# RTC.net
KiCad netlist of a schematic drawn in Altium Designer
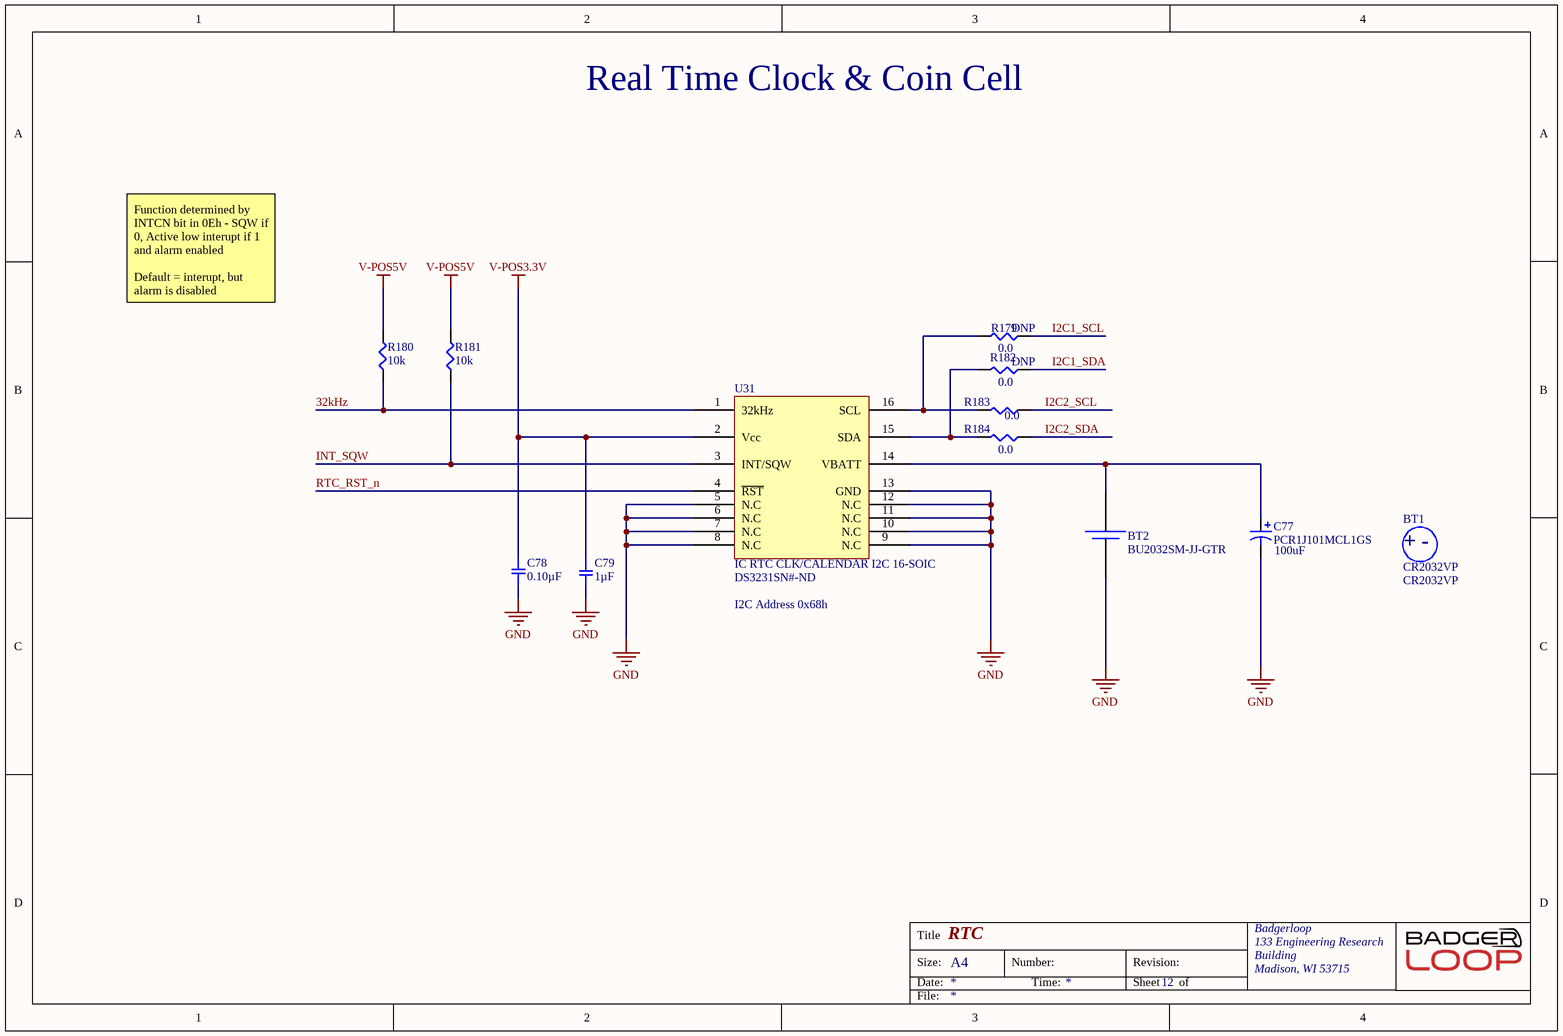
[diagram p0: RTC.SchDoc]

(export (version "E")
  (design (tool "Eeschema 10.0.6"))
  (components
    (comp (ref "BT1")
      (value "CR2032VP")
      (description "BATTERY LITHIUM 3V COIN 20MM")
      (fields (field (name "MANUFACTURER") "Energizer") (field (name "MANUFACTURER PART NUMBER") "CR2032VP"))
      (libsource (lib "misc") (part "CR2032VP"))
    )
    (comp (ref "BT2")
      (value "BU2032SM-JJ-GTR")
      (footprint "BATTERY HOLDER COIN 20MM")
      (description "HOLDER COIN CELL 2032 SMD")
      (fields (field (name "MANUFACTURER") "Memory Protection Devices"))
      (libsource (lib "misc") (part "BU2032SM-JJ-GTR"))
    )
    (comp (ref "C77")
      (value "PCR1J101MCL1GS")
      (footprint "CAPAE110103X126M")
      (description "CAP ALUM POLY 100UF 20% 63V SMD")
      (fields
        (field (name "MANUFACTURER") "Nichicon")
        (field (name "CAPACITANCE") "100uF")
        (field (name "TOLERANCE") "20%")
      )
      (libsource (lib "capacitors") (part "PCR1J101MCL1GS"))
    )
    (comp (ref "C78")
      (value "0.10µF")
      (footprint "SMD-0805C")
      (description "CAP CER 0.1UF 16V X7R 0805")
      (fields
        (field (name "DIGI-KEY PART NUMBER") "490-12557-1-ND")
        (field (name "PART NUMBER") "GRM219R71C104JA01D")
      )
      (libsource (lib "capacitors") (part "GRM219R71C104JA01D"))
    )
    (comp (ref "C79")
      (value "1µF")
      (footprint "SMD-0805C")
      (description "CAP CER 1UF 50V X7R 0805")
      (fields
        (field (name "DIGI-KEY PART NUMBER") "490-4736-1-ND")
        (field (name "PART NUMBER") "GRM21BR71H105KA12L")
      )
      (libsource (lib "capacitors") (part "GRM21BR71H105KA12L"))
    )
    (comp (ref "R179")
      (value "0.0")
      (footprint "SMD-0805-RES")
      (description "RES SMD 0.0 OHM JUMPER 1/8W 0805")
      (fields
        (field (name "PART NUMBER") "ERJ-6GEY0R00V")
        (field (name "DIGI-KEY PART NUMBER") "P0.0ACT-ND")
        (field (name "DNP") "DNP")
      )
      (libsource (lib "resistors") (part "ERJ-6GEY0R00V"))
    )
    (comp (ref "R180")
      (value "10k")
      (footprint "SMD-0805-RES")
      (description "RES SMD 10K OHM 5% 1/2W 0805")
      (fields (field (name "PART NUMBER") "ERJ-P06J103V") (field (name "DIGI-KEY PART NUMBER") "P10KADCT-ND"))
      (libsource (lib "resistors") (part "ERJ-P06J103V"))
    )
    (comp (ref "R181")
      (value "10k")
      (footprint "SMD-0805-RES")
      (description "RES SMD 10K OHM 5% 1/2W 0805")
      (fields (field (name "PART NUMBER") "ERJ-P06J103V") (field (name "DIGI-KEY PART NUMBER") "P10KADCT-ND"))
      (libsource (lib "resistors") (part "ERJ-P06J103V"))
    )
    (comp (ref "R182")
      (value "0.0")
      (footprint "SMD-0805-RES")
      (description "RES SMD 0.0 OHM JUMPER 1/8W 0805")
      (fields
        (field (name "PART NUMBER") "ERJ-6GEY0R00V")
        (field (name "DIGI-KEY PART NUMBER") "P0.0ACT-ND")
        (field (name "DNP") "DNP")
      )
      (libsource (lib "resistors") (part "ERJ-6GEY0R00V"))
    )
    (comp (ref "R183")
      (value "0.0")
      (footprint "SMD-0805-RES")
      (description "RES SMD 0.0 OHM JUMPER 1/8W 0805")
      (fields (field (name "PART NUMBER") "ERJ-6GEY0R00V") (field (name "DIGI-KEY PART NUMBER") "P0.0ACT-ND"))
      (libsource (lib "resistors") (part "ERJ-6GEY0R00V"))
    )
    (comp (ref "R184")
      (value "0.0")
      (footprint "SMD-0805-RES")
      (description "RES SMD 0.0 OHM JUMPER 1/8W 0805")
      (fields (field (name "PART NUMBER") "ERJ-6GEY0R00V") (field (name "DIGI-KEY PART NUMBER") "P0.0ACT-ND"))
      (libsource (lib "resistors") (part "ERJ-6GEY0R00V"))
    )
    (comp (ref "U31")
      (value "IC RTC CLK/CALENDAR I2C 16-SOIC")
      (footprint "SOP127P1030X265-16N")
      (fields
        (field (name "MANUFACTURER") "Maxim")
        (field (name "MANUFACTURER PART NUMBER") "DS3231SN#")
        (field (name "SUPPLIER PART NUMBER 1") "DS3231SN#-ND")
      )
      (libsource (lib "ic") (part "DS3231"))
    )
  )
  (nets
    (net (code "1") (name "/32kHz") (class "Default")
      (node (ref "R180") (pin "1") (pinfunction "1_1") (pintype "passive"))
      (node (ref "U31") (pin "1") (pinfunction "32kHz_1") (pintype "passive"))
    )
    (net (code "2") (name "/I2C1_SCL") (class "Default")
      (node (ref "R179") (pin "1") (pinfunction "1_1") (pintype "passive"))
    )
    (net (code "3") (name "/I2C1_SDA") (class "Default")
      (node (ref "R182") (pin "1") (pinfunction "1_1") (pintype "passive"))
    )
    (net (code "4") (name "/I2C2_SCL") (class "Default")
      (node (ref "R183") (pin "1") (pinfunction "1_1") (pintype "passive"))
    )
    (net (code "5") (name "/I2C2_SDA") (class "Default")
      (node (ref "R184") (pin "1") (pinfunction "1_1") (pintype "passive"))
    )
    (net (code "6") (name "/INT_SQW") (class "Default")
      (node (ref "R181") (pin "1") (pinfunction "1_1") (pintype "passive"))
      (node (ref "U31") (pin "3") (pinfunction "INT/SQW_3") (pintype "passive"))
    )
    (net (code "7") (name "/RTC_RST_n") (class "Default")
      (node (ref "U31") (pin "4") (pinfunction "RST_4") (pintype "passive"))
    )
    (net (code "8") (name "GND") (class "Default")
      (node (ref "BT2") (pin "1") (pinfunction "+_1") (pintype "passive"))
      (node (ref "C77") (pin "2") (pinfunction "2_2") (pintype "passive"))
      (node (ref "C78") (pin "1") (pinfunction "1_1") (pintype "passive"))
      (node (ref "C79") (pin "2") (pinfunction "2_2") (pintype "passive"))
      (node (ref "U31") (pin "10") (pinfunction "N.C_10") (pintype "passive"))
      (node (ref "U31") (pin "11") (pinfunction "N.C_11") (pintype "passive"))
      (node (ref "U31") (pin "12") (pinfunction "N.C_12") (pintype "passive"))
      (node (ref "U31") (pin "13") (pinfunction "GND_13") (pintype "passive"))
      (node (ref "U31") (pin "5") (pinfunction "N.C_5") (pintype "passive"))
      (node (ref "U31") (pin "6") (pinfunction "N.C_6") (pintype "passive"))
      (node (ref "U31") (pin "7") (pinfunction "N.C_7") (pintype "passive"))
      (node (ref "U31") (pin "8") (pinfunction "N.C_8") (pintype "passive"))
      (node (ref "U31") (pin "9") (pinfunction "N.C_9") (pintype "passive"))
    )
    (net (code "9") (name "Net-(BT2--)") (class "Default")
      (node (ref "BT2") (pin "2") (pinfunction "-_2") (pintype "passive"))
      (node (ref "C77") (pin "1") (pinfunction "1_1") (pintype "passive"))
      (node (ref "U31") (pin "14") (pinfunction "VBATT_14") (pintype "passive"))
    )
    (net (code "10") (name "Net-(U31-SCL)") (class "Default")
      (node (ref "R179") (pin "2") (pinfunction "2_2") (pintype "passive"))
      (node (ref "R183") (pin "2") (pinfunction "2_2") (pintype "passive"))
      (node (ref "U31") (pin "16") (pinfunction "SCL_16") (pintype "passive"))
    )
    (net (code "11") (name "Net-(U31-SDA)") (class "Default")
      (node (ref "R182") (pin "2") (pinfunction "2_2") (pintype "passive"))
      (node (ref "R184") (pin "2") (pinfunction "2_2") (pintype "passive"))
      (node (ref "U31") (pin "15") (pinfunction "SDA_15") (pintype "passive"))
    )
    (net (code "12") (name "V-POS3.3V") (class "Default")
      (node (ref "C78") (pin "2") (pinfunction "2_2") (pintype "passive"))
      (node (ref "C79") (pin "1") (pinfunction "1_1") (pintype "passive"))
      (node (ref "U31") (pin "2") (pinfunction "Vcc_2") (pintype "passive"))
    )
    (net (code "13") (name "V-POS5V") (class "Default")
      (node (ref "R180") (pin "2") (pinfunction "2_2") (pintype "passive"))
      (node (ref "R181") (pin "2") (pinfunction "2_2") (pintype "passive"))
    )
  )
)
